# LuMini_8X8.net
KiCad netlist of a schematic drawn in EAGLE
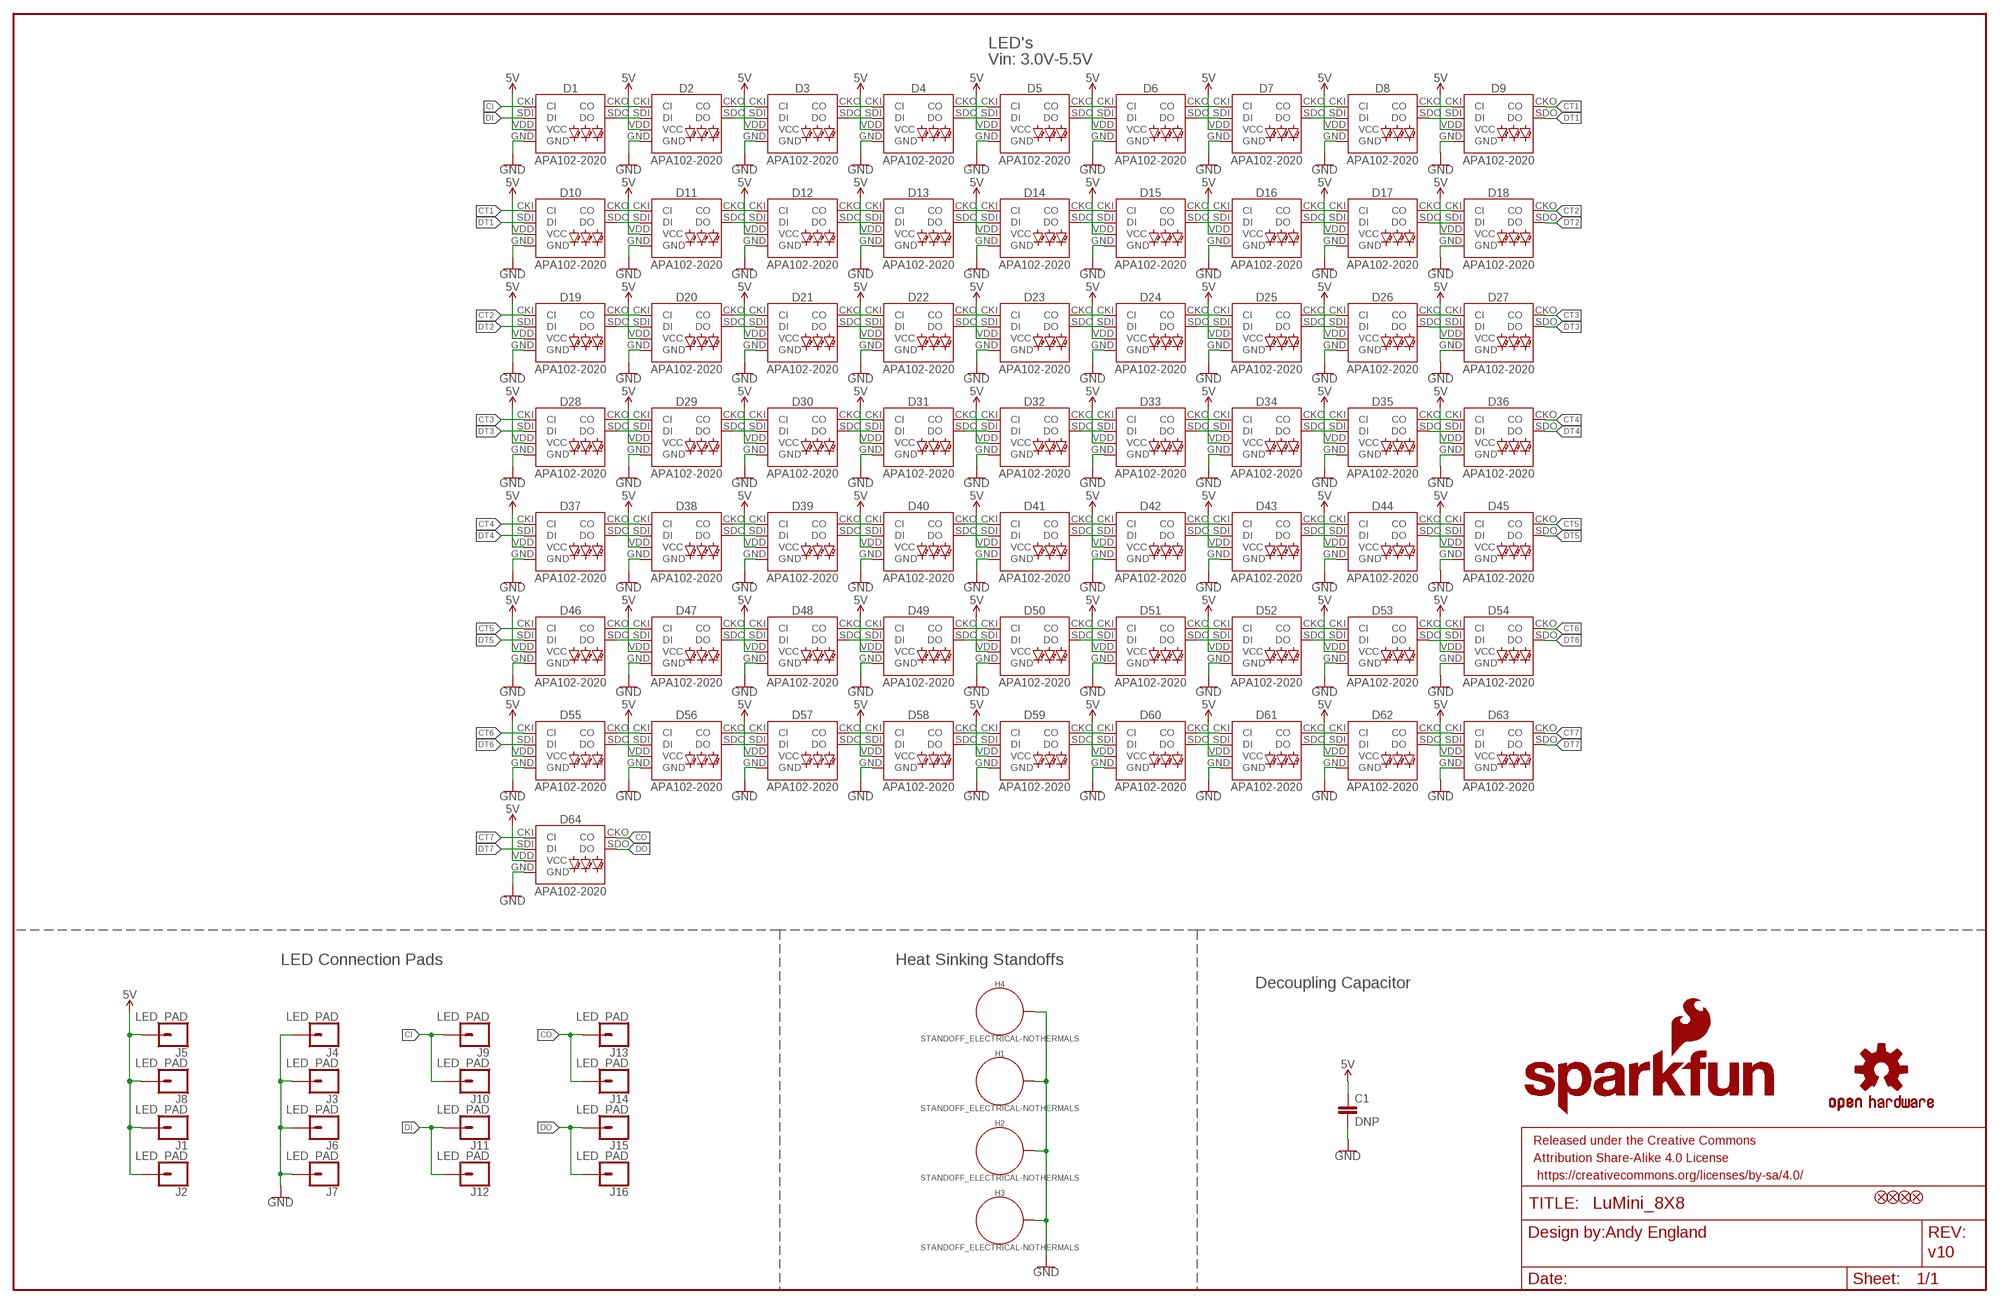
[diagram p0: schematic, sheet 1]

(export (version "E")
  (design (tool "Eeschema 10.0.6"))
  (components
    (comp (ref "C1")
      (value "DNP")
      (footprint "eagle-import:1206")
      (libsource (lib "eagle-import") (part "4.7UF-1206-16V-(+80/-20%)"))
    )
    (comp (ref "D1")
      (value "APA102-2020")
      (footprint "eagle-import:APA102-2020")
      (libsource (lib "eagle-import") (part "APA102-2020"))
    )
    (comp (ref "D2")
      (value "APA102-2020")
      (footprint "eagle-import:APA102-2020")
      (libsource (lib "eagle-import") (part "APA102-2020"))
    )
    (comp (ref "D3")
      (value "APA102-2020")
      (footprint "eagle-import:APA102-2020")
      (libsource (lib "eagle-import") (part "APA102-2020"))
    )
    (comp (ref "D4")
      (value "APA102-2020")
      (footprint "eagle-import:APA102-2020")
      (libsource (lib "eagle-import") (part "APA102-2020"))
    )
    (comp (ref "D5")
      (value "APA102-2020")
      (footprint "eagle-import:APA102-2020")
      (libsource (lib "eagle-import") (part "APA102-2020"))
    )
    (comp (ref "D6")
      (value "APA102-2020")
      (footprint "eagle-import:APA102-2020")
      (libsource (lib "eagle-import") (part "APA102-2020"))
    )
    (comp (ref "D7")
      (value "APA102-2020")
      (footprint "eagle-import:APA102-2020")
      (libsource (lib "eagle-import") (part "APA102-2020"))
    )
    (comp (ref "D8")
      (value "APA102-2020")
      (footprint "eagle-import:APA102-2020")
      (libsource (lib "eagle-import") (part "APA102-2020"))
    )
    (comp (ref "D9")
      (value "APA102-2020")
      (footprint "eagle-import:APA102-2020")
      (libsource (lib "eagle-import") (part "APA102-2020"))
    )
    (comp (ref "D10")
      (value "APA102-2020")
      (footprint "eagle-import:APA102-2020")
      (libsource (lib "eagle-import") (part "APA102-2020"))
    )
    (comp (ref "D11")
      (value "APA102-2020")
      (footprint "eagle-import:APA102-2020")
      (libsource (lib "eagle-import") (part "APA102-2020"))
    )
    (comp (ref "D12")
      (value "APA102-2020")
      (footprint "eagle-import:APA102-2020")
      (libsource (lib "eagle-import") (part "APA102-2020"))
    )
    (comp (ref "D13")
      (value "APA102-2020")
      (footprint "eagle-import:APA102-2020")
      (libsource (lib "eagle-import") (part "APA102-2020"))
    )
    (comp (ref "D14")
      (value "APA102-2020")
      (footprint "eagle-import:APA102-2020")
      (libsource (lib "eagle-import") (part "APA102-2020"))
    )
    (comp (ref "D15")
      (value "APA102-2020")
      (footprint "eagle-import:APA102-2020")
      (libsource (lib "eagle-import") (part "APA102-2020"))
    )
    (comp (ref "D16")
      (value "APA102-2020")
      (footprint "eagle-import:APA102-2020")
      (libsource (lib "eagle-import") (part "APA102-2020"))
    )
    (comp (ref "D17")
      (value "APA102-2020")
      (footprint "eagle-import:APA102-2020")
      (libsource (lib "eagle-import") (part "APA102-2020"))
    )
    (comp (ref "D18")
      (value "APA102-2020")
      (footprint "eagle-import:APA102-2020")
      (libsource (lib "eagle-import") (part "APA102-2020"))
    )
    (comp (ref "D19")
      (value "APA102-2020")
      (footprint "eagle-import:APA102-2020")
      (libsource (lib "eagle-import") (part "APA102-2020"))
    )
    (comp (ref "D20")
      (value "APA102-2020")
      (footprint "eagle-import:APA102-2020")
      (libsource (lib "eagle-import") (part "APA102-2020"))
    )
    (comp (ref "D21")
      (value "APA102-2020")
      (footprint "eagle-import:APA102-2020")
      (libsource (lib "eagle-import") (part "APA102-2020"))
    )
    (comp (ref "D22")
      (value "APA102-2020")
      (footprint "eagle-import:APA102-2020")
      (libsource (lib "eagle-import") (part "APA102-2020"))
    )
    (comp (ref "D23")
      (value "APA102-2020")
      (footprint "eagle-import:APA102-2020")
      (libsource (lib "eagle-import") (part "APA102-2020"))
    )
    (comp (ref "D24")
      (value "APA102-2020")
      (footprint "eagle-import:APA102-2020")
      (libsource (lib "eagle-import") (part "APA102-2020"))
    )
    (comp (ref "D25")
      (value "APA102-2020")
      (footprint "eagle-import:APA102-2020")
      (libsource (lib "eagle-import") (part "APA102-2020"))
    )
    (comp (ref "D26")
      (value "APA102-2020")
      (footprint "eagle-import:APA102-2020")
      (libsource (lib "eagle-import") (part "APA102-2020"))
    )
    (comp (ref "D27")
      (value "APA102-2020")
      (footprint "eagle-import:APA102-2020")
      (libsource (lib "eagle-import") (part "APA102-2020"))
    )
    (comp (ref "D28")
      (value "APA102-2020")
      (footprint "eagle-import:APA102-2020")
      (libsource (lib "eagle-import") (part "APA102-2020"))
    )
    (comp (ref "D29")
      (value "APA102-2020")
      (footprint "eagle-import:APA102-2020")
      (libsource (lib "eagle-import") (part "APA102-2020"))
    )
    (comp (ref "D30")
      (value "APA102-2020")
      (footprint "eagle-import:APA102-2020")
      (libsource (lib "eagle-import") (part "APA102-2020"))
    )
    (comp (ref "D31")
      (value "APA102-2020")
      (footprint "eagle-import:APA102-2020")
      (libsource (lib "eagle-import") (part "APA102-2020"))
    )
    (comp (ref "D32")
      (value "APA102-2020")
      (footprint "eagle-import:APA102-2020")
      (libsource (lib "eagle-import") (part "APA102-2020"))
    )
    (comp (ref "D33")
      (value "APA102-2020")
      (footprint "eagle-import:APA102-2020")
      (libsource (lib "eagle-import") (part "APA102-2020"))
    )
    (comp (ref "D34")
      (value "APA102-2020")
      (footprint "eagle-import:APA102-2020")
      (libsource (lib "eagle-import") (part "APA102-2020"))
    )
    (comp (ref "D35")
      (value "APA102-2020")
      (footprint "eagle-import:APA102-2020")
      (libsource (lib "eagle-import") (part "APA102-2020"))
    )
    (comp (ref "D36")
      (value "APA102-2020")
      (footprint "eagle-import:APA102-2020")
      (libsource (lib "eagle-import") (part "APA102-2020"))
    )
    (comp (ref "D37")
      (value "APA102-2020")
      (footprint "eagle-import:APA102-2020")
      (libsource (lib "eagle-import") (part "APA102-2020"))
    )
    (comp (ref "D38")
      (value "APA102-2020")
      (footprint "eagle-import:APA102-2020")
      (libsource (lib "eagle-import") (part "APA102-2020"))
    )
    (comp (ref "D39")
      (value "APA102-2020")
      (footprint "eagle-import:APA102-2020")
      (libsource (lib "eagle-import") (part "APA102-2020"))
    )
    (comp (ref "D40")
      (value "APA102-2020")
      (footprint "eagle-import:APA102-2020")
      (libsource (lib "eagle-import") (part "APA102-2020"))
    )
    (comp (ref "D41")
      (value "APA102-2020")
      (footprint "eagle-import:APA102-2020")
      (libsource (lib "eagle-import") (part "APA102-2020"))
    )
    (comp (ref "D42")
      (value "APA102-2020")
      (footprint "eagle-import:APA102-2020")
      (libsource (lib "eagle-import") (part "APA102-2020"))
    )
    (comp (ref "D43")
      (value "APA102-2020")
      (footprint "eagle-import:APA102-2020")
      (libsource (lib "eagle-import") (part "APA102-2020"))
    )
    (comp (ref "D44")
      (value "APA102-2020")
      (footprint "eagle-import:APA102-2020")
      (libsource (lib "eagle-import") (part "APA102-2020"))
    )
    (comp (ref "D45")
      (value "APA102-2020")
      (footprint "eagle-import:APA102-2020")
      (libsource (lib "eagle-import") (part "APA102-2020"))
    )
    (comp (ref "D46")
      (value "APA102-2020")
      (footprint "eagle-import:APA102-2020")
      (libsource (lib "eagle-import") (part "APA102-2020"))
    )
    (comp (ref "D47")
      (value "APA102-2020")
      (footprint "eagle-import:APA102-2020")
      (libsource (lib "eagle-import") (part "APA102-2020"))
    )
    (comp (ref "D48")
      (value "APA102-2020")
      (footprint "eagle-import:APA102-2020")
      (libsource (lib "eagle-import") (part "APA102-2020"))
    )
    (comp (ref "D49")
      (value "APA102-2020")
      (footprint "eagle-import:APA102-2020")
      (libsource (lib "eagle-import") (part "APA102-2020"))
    )
    (comp (ref "D50")
      (value "APA102-2020")
      (footprint "eagle-import:APA102-2020")
      (libsource (lib "eagle-import") (part "APA102-2020"))
    )
    (comp (ref "D51")
      (value "APA102-2020")
      (footprint "eagle-import:APA102-2020")
      (libsource (lib "eagle-import") (part "APA102-2020"))
    )
    (comp (ref "D52")
      (value "APA102-2020")
      (footprint "eagle-import:APA102-2020")
      (libsource (lib "eagle-import") (part "APA102-2020"))
    )
    (comp (ref "D53")
      (value "APA102-2020")
      (footprint "eagle-import:APA102-2020")
      (libsource (lib "eagle-import") (part "APA102-2020"))
    )
    (comp (ref "D54")
      (value "APA102-2020")
      (footprint "eagle-import:APA102-2020")
      (libsource (lib "eagle-import") (part "APA102-2020"))
    )
    (comp (ref "D55")
      (value "APA102-2020")
      (footprint "eagle-import:APA102-2020")
      (libsource (lib "eagle-import") (part "APA102-2020"))
    )
    (comp (ref "D56")
      (value "APA102-2020")
      (footprint "eagle-import:APA102-2020")
      (libsource (lib "eagle-import") (part "APA102-2020"))
    )
    (comp (ref "D57")
      (value "APA102-2020")
      (footprint "eagle-import:APA102-2020")
      (libsource (lib "eagle-import") (part "APA102-2020"))
    )
    (comp (ref "D58")
      (value "APA102-2020")
      (footprint "eagle-import:APA102-2020")
      (libsource (lib "eagle-import") (part "APA102-2020"))
    )
    (comp (ref "D59")
      (value "APA102-2020")
      (footprint "eagle-import:APA102-2020")
      (libsource (lib "eagle-import") (part "APA102-2020"))
    )
    (comp (ref "D60")
      (value "APA102-2020")
      (footprint "eagle-import:APA102-2020")
      (libsource (lib "eagle-import") (part "APA102-2020"))
    )
    (comp (ref "D61")
      (value "APA102-2020")
      (footprint "eagle-import:APA102-2020")
      (libsource (lib "eagle-import") (part "APA102-2020"))
    )
    (comp (ref "D62")
      (value "APA102-2020")
      (footprint "eagle-import:APA102-2020")
      (libsource (lib "eagle-import") (part "APA102-2020"))
    )
    (comp (ref "D63")
      (value "APA102-2020")
      (footprint "eagle-import:APA102-2020")
      (libsource (lib "eagle-import") (part "APA102-2020"))
    )
    (comp (ref "D64")
      (value "APA102-2020")
      (footprint "eagle-import:APA102-2020")
      (libsource (lib "eagle-import") (part "APA102-2020"))
    )
    (comp (ref "FD1")
      (value "FIDUCIALUFIDUCIAL")
      (footprint "eagle-import:FIDUCIAL-MICRO")
      (libsource (lib "eagle-import") (part "FIDUCIALUFIDUCIAL"))
    )
    (comp (ref "FD2")
      (value "FIDUCIALUFIDUCIAL")
      (footprint "eagle-import:FIDUCIAL-MICRO")
      (libsource (lib "eagle-import") (part "FIDUCIALUFIDUCIAL"))
    )
    (comp (ref "FD3")
      (value "FIDUCIALUFIDUCIAL")
      (footprint "eagle-import:FIDUCIAL-MICRO")
      (libsource (lib "eagle-import") (part "FIDUCIALUFIDUCIAL"))
    )
    (comp (ref "FD4")
      (value "FIDUCIALUFIDUCIAL")
      (footprint "eagle-import:FIDUCIAL-MICRO")
      (libsource (lib "eagle-import") (part "FIDUCIALUFIDUCIAL"))
    )
    (comp (ref "FRAME1")
      (value "FRAME-LEDGER")
      (footprint "eagle-import:CREATIVE_COMMONS")
      (libsource (lib "eagle-import") (part "FRAME-LEDGER"))
    )
    (comp (ref "H1")
      (value "STANDOFF_ELECTRICAL-NOTHERMALS")
      (footprint "eagle-import:STANDOFF-ELECTRICAL-NOTHERMALS")
      (libsource (lib "eagle-import") (part "STANDOFF_ELECTRICAL-NOTHERMALS"))
    )
    (comp (ref "H2")
      (value "STANDOFF_ELECTRICAL-NOTHERMALS")
      (footprint "eagle-import:STANDOFF-ELECTRICAL-NOTHERMALS")
      (libsource (lib "eagle-import") (part "STANDOFF_ELECTRICAL-NOTHERMALS"))
    )
    (comp (ref "H3")
      (value "STANDOFF_ELECTRICAL-NOTHERMALS")
      (footprint "eagle-import:STANDOFF-ELECTRICAL-NOTHERMALS")
      (libsource (lib "eagle-import") (part "STANDOFF_ELECTRICAL-NOTHERMALS"))
    )
    (comp (ref "H4")
      (value "STANDOFF_ELECTRICAL-NOTHERMALS")
      (footprint "eagle-import:STANDOFF-ELECTRICAL-NOTHERMALS")
      (libsource (lib "eagle-import") (part "STANDOFF_ELECTRICAL-NOTHERMALS"))
    )
    (comp (ref "J1")
      (value "LED_PAD")
      (footprint "eagle-import:CIRCULARPAD")
      (libsource (lib "eagle-import") (part "LED_PAD"))
    )
    (comp (ref "J2")
      (value "LED_PAD")
      (footprint "eagle-import:CIRCULARPAD")
      (libsource (lib "eagle-import") (part "LED_PAD"))
    )
    (comp (ref "J3")
      (value "LED_PAD")
      (footprint "eagle-import:CIRCULARPAD")
      (libsource (lib "eagle-import") (part "LED_PAD"))
    )
    (comp (ref "J4")
      (value "LED_PAD")
      (footprint "eagle-import:CIRCULARPAD")
      (libsource (lib "eagle-import") (part "LED_PAD"))
    )
    (comp (ref "J5")
      (value "LED_PAD")
      (footprint "eagle-import:CIRCULARPAD")
      (libsource (lib "eagle-import") (part "LED_PAD"))
    )
    (comp (ref "J6")
      (value "LED_PAD")
      (footprint "eagle-import:CIRCULARPAD")
      (libsource (lib "eagle-import") (part "LED_PAD"))
    )
    (comp (ref "J7")
      (value "LED_PAD")
      (footprint "eagle-import:CIRCULARPAD")
      (libsource (lib "eagle-import") (part "LED_PAD"))
    )
    (comp (ref "J8")
      (value "LED_PAD")
      (footprint "eagle-import:CIRCULARPAD")
      (libsource (lib "eagle-import") (part "LED_PAD"))
    )
    (comp (ref "J9")
      (value "LED_PAD")
      (footprint "eagle-import:CIRCULARPAD")
      (libsource (lib "eagle-import") (part "LED_PAD"))
    )
    (comp (ref "J10")
      (value "LED_PAD")
      (footprint "eagle-import:CIRCULARPAD")
      (libsource (lib "eagle-import") (part "LED_PAD"))
    )
    (comp (ref "J11")
      (value "LED_PAD")
      (footprint "eagle-import:CIRCULARPAD")
      (libsource (lib "eagle-import") (part "LED_PAD"))
    )
    (comp (ref "J12")
      (value "LED_PAD")
      (footprint "eagle-import:CIRCULARPAD")
      (libsource (lib "eagle-import") (part "LED_PAD"))
    )
    (comp (ref "J13")
      (value "LED_PAD")
      (footprint "eagle-import:CIRCULARPAD")
      (libsource (lib "eagle-import") (part "LED_PAD"))
    )
    (comp (ref "J14")
      (value "LED_PAD")
      (footprint "eagle-import:CIRCULARPAD")
      (libsource (lib "eagle-import") (part "LED_PAD"))
    )
    (comp (ref "J15")
      (value "LED_PAD")
      (footprint "eagle-import:CIRCULARPAD")
      (libsource (lib "eagle-import") (part "LED_PAD"))
    )
    (comp (ref "J16")
      (value "LED_PAD")
      (footprint "eagle-import:CIRCULARPAD")
      (libsource (lib "eagle-import") (part "LED_PAD"))
    )
    (comp (ref "LOGO1")
      (value "SFE_LOGO_NAME_FLAME.1_INCH")
      (footprint "eagle-import:SFE_LOGO_NAME_FLAME_.1")
      (libsource (lib "eagle-import") (part "SFE_LOGO_NAME_FLAME.1_INCH"))
    )
    (comp (ref "LOGO2")
      (value "OSHW-LOGOS")
      (footprint "eagle-import:OSHW-LOGO-S")
      (libsource (lib "eagle-import") (part "OSHW-LOGOS"))
    )
  )
  (nets
    (net (code "1") (name "5V") (class "Default")
      (node (ref "C1") (pin "1") (pinfunction "1_1") (pintype "passive"))
      (node (ref "D1") (pin "VDD") (pinfunction "VCC_VDD") (pintype "bidirectional"))
      (node (ref "D10") (pin "VDD") (pinfunction "VCC_VDD") (pintype "bidirectional"))
      (node (ref "D11") (pin "VDD") (pinfunction "VCC_VDD") (pintype "bidirectional"))
      (node (ref "D12") (pin "VDD") (pinfunction "VCC_VDD") (pintype "bidirectional"))
      (node (ref "D13") (pin "VDD") (pinfunction "VCC_VDD") (pintype "bidirectional"))
      (node (ref "D14") (pin "VDD") (pinfunction "VCC_VDD") (pintype "bidirectional"))
      (node (ref "D15") (pin "VDD") (pinfunction "VCC_VDD") (pintype "bidirectional"))
      (node (ref "D16") (pin "VDD") (pinfunction "VCC_VDD") (pintype "bidirectional"))
      (node (ref "D17") (pin "VDD") (pinfunction "VCC_VDD") (pintype "bidirectional"))
      (node (ref "D18") (pin "VDD") (pinfunction "VCC_VDD") (pintype "bidirectional"))
      (node (ref "D19") (pin "VDD") (pinfunction "VCC_VDD") (pintype "bidirectional"))
      (node (ref "D2") (pin "VDD") (pinfunction "VCC_VDD") (pintype "bidirectional"))
      (node (ref "D20") (pin "VDD") (pinfunction "VCC_VDD") (pintype "bidirectional"))
      (node (ref "D21") (pin "VDD") (pinfunction "VCC_VDD") (pintype "bidirectional"))
      (node (ref "D22") (pin "VDD") (pinfunction "VCC_VDD") (pintype "bidirectional"))
      (node (ref "D23") (pin "VDD") (pinfunction "VCC_VDD") (pintype "bidirectional"))
      (node (ref "D24") (pin "VDD") (pinfunction "VCC_VDD") (pintype "bidirectional"))
      (node (ref "D25") (pin "VDD") (pinfunction "VCC_VDD") (pintype "bidirectional"))
      (node (ref "D26") (pin "VDD") (pinfunction "VCC_VDD") (pintype "bidirectional"))
      (node (ref "D27") (pin "VDD") (pinfunction "VCC_VDD") (pintype "bidirectional"))
      (node (ref "D28") (pin "VDD") (pinfunction "VCC_VDD") (pintype "bidirectional"))
      (node (ref "D29") (pin "VDD") (pinfunction "VCC_VDD") (pintype "bidirectional"))
      (node (ref "D3") (pin "VDD") (pinfunction "VCC_VDD") (pintype "bidirectional"))
      (node (ref "D30") (pin "VDD") (pinfunction "VCC_VDD") (pintype "bidirectional"))
      (node (ref "D31") (pin "VDD") (pinfunction "VCC_VDD") (pintype "bidirectional"))
      (node (ref "D32") (pin "VDD") (pinfunction "VCC_VDD") (pintype "bidirectional"))
      (node (ref "D33") (pin "VDD") (pinfunction "VCC_VDD") (pintype "bidirectional"))
      (node (ref "D34") (pin "VDD") (pinfunction "VCC_VDD") (pintype "bidirectional"))
      (node (ref "D35") (pin "VDD") (pinfunction "VCC_VDD") (pintype "bidirectional"))
      (node (ref "D36") (pin "VDD") (pinfunction "VCC_VDD") (pintype "bidirectional"))
      (node (ref "D37") (pin "VDD") (pinfunction "VCC_VDD") (pintype "bidirectional"))
      (node (ref "D38") (pin "VDD") (pinfunction "VCC_VDD") (pintype "bidirectional"))
      (node (ref "D39") (pin "VDD") (pinfunction "VCC_VDD") (pintype "bidirectional"))
      (node (ref "D4") (pin "VDD") (pinfunction "VCC_VDD") (pintype "bidirectional"))
      (node (ref "D40") (pin "VDD") (pinfunction "VCC_VDD") (pintype "bidirectional"))
      (node (ref "D41") (pin "VDD") (pinfunction "VCC_VDD") (pintype "bidirectional"))
      (node (ref "D42") (pin "VDD") (pinfunction "VCC_VDD") (pintype "bidirectional"))
      (node (ref "D43") (pin "VDD") (pinfunction "VCC_VDD") (pintype "bidirectional"))
      (node (ref "D44") (pin "VDD") (pinfunction "VCC_VDD") (pintype "bidirectional"))
      (node (ref "D45") (pin "VDD") (pinfunction "VCC_VDD") (pintype "bidirectional"))
      (node (ref "D46") (pin "VDD") (pinfunction "VCC_VDD") (pintype "bidirectional"))
      (node (ref "D47") (pin "VDD") (pinfunction "VCC_VDD") (pintype "bidirectional"))
      (node (ref "D48") (pin "VDD") (pinfunction "VCC_VDD") (pintype "bidirectional"))
      (node (ref "D49") (pin "VDD") (pinfunction "VCC_VDD") (pintype "bidirectional"))
      (node (ref "D5") (pin "VDD") (pinfunction "VCC_VDD") (pintype "bidirectional"))
      (node (ref "D50") (pin "VDD") (pinfunction "VCC_VDD") (pintype "bidirectional"))
      (node (ref "D51") (pin "VDD") (pinfunction "VCC_VDD") (pintype "bidirectional"))
      (node (ref "D52") (pin "VDD") (pinfunction "VCC_VDD") (pintype "bidirectional"))
      (node (ref "D53") (pin "VDD") (pinfunction "VCC_VDD") (pintype "bidirectional"))
      (node (ref "D54") (pin "VDD") (pinfunction "VCC_VDD") (pintype "bidirectional"))
      (node (ref "D55") (pin "VDD") (pinfunction "VCC_VDD") (pintype "bidirectional"))
      (node (ref "D56") (pin "VDD") (pinfunction "VCC_VDD") (pintype "bidirectional"))
      (node (ref "D57") (pin "VDD") (pinfunction "VCC_VDD") (pintype "bidirectional"))
      (node (ref "D58") (pin "VDD") (pinfunction "VCC_VDD") (pintype "bidirectional"))
      (node (ref "D59") (pin "VDD") (pinfunction "VCC_VDD") (pintype "bidirectional"))
      (node (ref "D6") (pin "VDD") (pinfunction "VCC_VDD") (pintype "bidirectional"))
      (node (ref "D60") (pin "VDD") (pinfunction "VCC_VDD") (pintype "bidirectional"))
      (node (ref "D61") (pin "VDD") (pinfunction "VCC_VDD") (pintype "bidirectional"))
      (node (ref "D62") (pin "VDD") (pinfunction "VCC_VDD") (pintype "bidirectional"))
      (node (ref "D63") (pin "VDD") (pinfunction "VCC_VDD") (pintype "bidirectional"))
      (node (ref "D64") (pin "VDD") (pinfunction "VCC_VDD") (pintype "bidirectional"))
      (node (ref "D7") (pin "VDD") (pinfunction "VCC_VDD") (pintype "bidirectional"))
      (node (ref "D8") (pin "VDD") (pinfunction "VCC_VDD") (pintype "bidirectional"))
      (node (ref "D9") (pin "VDD") (pinfunction "VCC_VDD") (pintype "bidirectional"))
      (node (ref "J1") (pin "P$1") (pinfunction "1_P$1") (pintype "passive"))
      (node (ref "J1") (pin "P$2") (pinfunction "1_P$2") (pintype "passive"))
      (node (ref "J2") (pin "P$1") (pinfunction "1_P$1") (pintype "passive"))
      (node (ref "J2") (pin "P$2") (pinfunction "1_P$2") (pintype "passive"))
      (node (ref "J5") (pin "P$1") (pinfunction "1_P$1") (pintype "passive"))
      (node (ref "J5") (pin "P$2") (pinfunction "1_P$2") (pintype "passive"))
      (node (ref "J8") (pin "P$1") (pinfunction "1_P$1") (pintype "passive"))
      (node (ref "J8") (pin "P$2") (pinfunction "1_P$2") (pintype "passive"))
    )
    (net (code "2") (name "CI") (class "Default")
      (node (ref "D1") (pin "CKI") (pinfunction "CI_CKI") (pintype "bidirectional"))
      (node (ref "J10") (pin "P$1") (pinfunction "1_P$1") (pintype "passive"))
      (node (ref "J10") (pin "P$2") (pinfunction "1_P$2") (pintype "passive"))
      (node (ref "J9") (pin "P$1") (pinfunction "1_P$1") (pintype "passive"))
      (node (ref "J9") (pin "P$2") (pinfunction "1_P$2") (pintype "passive"))
    )
    (net (code "3") (name "CO") (class "Default")
      (node (ref "D64") (pin "CKO") (pinfunction "CO_CKO") (pintype "bidirectional"))
      (node (ref "J13") (pin "P$1") (pinfunction "1_P$1") (pintype "passive"))
      (node (ref "J13") (pin "P$2") (pinfunction "1_P$2") (pintype "passive"))
      (node (ref "J14") (pin "P$1") (pinfunction "1_P$1") (pintype "passive"))
      (node (ref "J14") (pin "P$2") (pinfunction "1_P$2") (pintype "passive"))
    )
    (net (code "4") (name "CT1") (class "Default")
      (node (ref "D10") (pin "CKI") (pinfunction "CI_CKI") (pintype "bidirectional"))
      (node (ref "D9") (pin "CKO") (pinfunction "CO_CKO") (pintype "bidirectional"))
    )
    (net (code "5") (name "CT2") (class "Default")
      (node (ref "D18") (pin "CKO") (pinfunction "CO_CKO") (pintype "bidirectional"))
      (node (ref "D19") (pin "CKI") (pinfunction "CI_CKI") (pintype "bidirectional"))
    )
    (net (code "6") (name "CT3") (class "Default")
      (node (ref "D27") (pin "CKO") (pinfunction "CO_CKO") (pintype "bidirectional"))
      (node (ref "D28") (pin "CKI") (pinfunction "CI_CKI") (pintype "bidirectional"))
    )
    (net (code "7") (name "CT4") (class "Default")
      (node (ref "D36") (pin "CKO") (pinfunction "CO_CKO") (pintype "bidirectional"))
      (node (ref "D37") (pin "CKI") (pinfunction "CI_CKI") (pintype "bidirectional"))
    )
    (net (code "8") (name "CT5") (class "Default")
      (node (ref "D45") (pin "CKO") (pinfunction "CO_CKO") (pintype "bidirectional"))
      (node (ref "D46") (pin "CKI") (pinfunction "CI_CKI") (pintype "bidirectional"))
    )
    (net (code "9") (name "CT6") (class "Default")
      (node (ref "D54") (pin "CKO") (pinfunction "CO_CKO") (pintype "bidirectional"))
      (node (ref "D55") (pin "CKI") (pinfunction "CI_CKI") (pintype "bidirectional"))
    )
    (net (code "10") (name "CT7") (class "Default")
      (node (ref "D63") (pin "CKO") (pinfunction "CO_CKO") (pintype "bidirectional"))
      (node (ref "D64") (pin "CKI") (pinfunction "CI_CKI") (pintype "bidirectional"))
    )
    (net (code "11") (name "DI") (class "Default")
      (node (ref "D1") (pin "SDI") (pinfunction "DI_SDI") (pintype "bidirectional"))
      (node (ref "J11") (pin "P$1") (pinfunction "1_P$1") (pintype "passive"))
      (node (ref "J11") (pin "P$2") (pinfunction "1_P$2") (pintype "passive"))
      (node (ref "J12") (pin "P$1") (pinfunction "1_P$1") (pintype "passive"))
      (node (ref "J12") (pin "P$2") (pinfunction "1_P$2") (pintype "passive"))
    )
    (net (code "12") (name "DO") (class "Default")
      (node (ref "D64") (pin "SDO") (pinfunction "DO_SDO") (pintype "bidirectional"))
      (node (ref "J15") (pin "P$1") (pinfunction "1_P$1") (pintype "passive"))
      (node (ref "J15") (pin "P$2") (pinfunction "1_P$2") (pintype "passive"))
      (node (ref "J16") (pin "P$1") (pinfunction "1_P$1") (pintype "passive"))
      (node (ref "J16") (pin "P$2") (pinfunction "1_P$2") (pintype "passive"))
    )
    (net (code "13") (name "DT1") (class "Default")
      (node (ref "D10") (pin "SDI") (pinfunction "DI_SDI") (pintype "bidirectional"))
      (node (ref "D9") (pin "SDO") (pinfunction "DO_SDO") (pintype "bidirectional"))
    )
    (net (code "14") (name "DT2") (class "Default")
      (node (ref "D18") (pin "SDO") (pinfunction "DO_SDO") (pintype "bidirectional"))
      (node (ref "D19") (pin "SDI") (pinfunction "DI_SDI") (pintype "bidirectional"))
    )
    (net (code "15") (name "DT3") (class "Default")
      (node (ref "D27") (pin "SDO") (pinfunction "DO_SDO") (pintype "bidirectional"))
      (node (ref "D28") (pin "SDI") (pinfunction "DI_SDI") (pintype "bidirectional"))
    )
    (net (code "16") (name "DT4") (class "Default")
      (node (ref "D36") (pin "SDO") (pinfunction "DO_SDO") (pintype "bidirectional"))
      (node (ref "D37") (pin "SDI") (pinfunction "DI_SDI") (pintype "bidirectional"))
    )
    (net (code "17") (name "DT5") (class "Default")
      (node (ref "D45") (pin "SDO") (pinfunction "DO_SDO") (pintype "bidirectional"))
      (node (ref "D46") (pin "SDI") (pinfunction "DI_SDI") (pintype "bidirectional"))
    )
    (net (code "18") (name "DT6") (class "Default")
      (node (ref "D54") (pin "SDO") (pinfunction "DO_SDO") (pintype "bidirectional"))
      (node (ref "D55") (pin "SDI") (pinfunction "DI_SDI") (pintype "bidirectional"))
    )
    (net (code "19") (name "DT7") (class "Default")
      (node (ref "D63") (pin "SDO") (pinfunction "DO_SDO") (pintype "bidirectional"))
      (node (ref "D64") (pin "SDI") (pinfunction "DI_SDI") (pintype "bidirectional"))
    )
    (net (code "20") (name "GND") (class "Default")
      (node (ref "C1") (pin "2") (pinfunction "2_2") (pintype "passive"))
      (node (ref "D1") (pin "GND") (pinfunction "GND_GND") (pintype "bidirectional"))
      (node (ref "D10") (pin "GND") (pinfunction "GND_GND") (pintype "bidirectional"))
      (node (ref "D11") (pin "GND") (pinfunction "GND_GND") (pintype "bidirectional"))
      (node (ref "D12") (pin "GND") (pinfunction "GND_GND") (pintype "bidirectional"))
      (node (ref "D13") (pin "GND") (pinfunction "GND_GND") (pintype "bidirectional"))
      (node (ref "D14") (pin "GND") (pinfunction "GND_GND") (pintype "bidirectional"))
      (node (ref "D15") (pin "GND") (pinfunction "GND_GND") (pintype "bidirectional"))
      (node (ref "D16") (pin "GND") (pinfunction "GND_GND") (pintype "bidirectional"))
      (node (ref "D17") (pin "GND") (pinfunction "GND_GND") (pintype "bidirectional"))
      (node (ref "D18") (pin "GND") (pinfunction "GND_GND") (pintype "bidirectional"))
      (node (ref "D19") (pin "GND") (pinfunction "GND_GND") (pintype "bidirectional"))
      (node (ref "D2") (pin "GND") (pinfunction "GND_GND") (pintype "bidirectional"))
      (node (ref "D20") (pin "GND") (pinfunction "GND_GND") (pintype "bidirectional"))
      (node (ref "D21") (pin "GND") (pinfunction "GND_GND") (pintype "bidirectional"))
      (node (ref "D22") (pin "GND") (pinfunction "GND_GND") (pintype "bidirectional"))
      (node (ref "D23") (pin "GND") (pinfunction "GND_GND") (pintype "bidirectional"))
      (node (ref "D24") (pin "GND") (pinfunction "GND_GND") (pintype "bidirectional"))
      (node (ref "D25") (pin "GND") (pinfunction "GND_GND") (pintype "bidirectional"))
      (node (ref "D26") (pin "GND") (pinfunction "GND_GND") (pintype "bidirectional"))
      (node (ref "D27") (pin "GND") (pinfunction "GND_GND") (pintype "bidirectional"))
      (node (ref "D28") (pin "GND") (pinfunction "GND_GND") (pintype "bidirectional"))
      (node (ref "D29") (pin "GND") (pinfunction "GND_GND") (pintype "bidirectional"))
      (node (ref "D3") (pin "GND") (pinfunction "GND_GND") (pintype "bidirectional"))
      (node (ref "D30") (pin "GND") (pinfunction "GND_GND") (pintype "bidirectional"))
      (node (ref "D31") (pin "GND") (pinfunction "GND_GND") (pintype "bidirectional"))
      (node (ref "D32") (pin "GND") (pinfunction "GND_GND") (pintype "bidirectional"))
      (node (ref "D33") (pin "GND") (pinfunction "GND_GND") (pintype "bidirectional"))
      (node (ref "D34") (pin "GND") (pinfunction "GND_GND") (pintype "bidirectional"))
      (node (ref "D35") (pin "GND") (pinfunction "GND_GND") (pintype "bidirectional"))
      (node (ref "D36") (pin "GND") (pinfunction "GND_GND") (pintype "bidirectional"))
      (node (ref "D37") (pin "GND") (pinfunction "GND_GND") (pintype "bidirectional"))
      (node (ref "D38") (pin "GND") (pinfunction "GND_GND") (pintype "bidirectional"))
      (node (ref "D39") (pin "GND") (pinfunction "GND_GND") (pintype "bidirectional"))
      (node (ref "D4") (pin "GND") (pinfunction "GND_GND") (pintype "bidirectional"))
      (node (ref "D40") (pin "GND") (pinfunction "GND_GND") (pintype "bidirectional"))
      (node (ref "D41") (pin "GND") (pinfunction "GND_GND") (pintype "bidirectional"))
      (node (ref "D42") (pin "GND") (pinfunction "GND_GND") (pintype "bidirectional"))
      (node (ref "D43") (pin "GND") (pinfunction "GND_GND") (pintype "bidirectional"))
      (node (ref "D44") (pin "GND") (pinfunction "GND_GND") (pintype "bidirectional"))
      (node (ref "D45") (pin "GND") (pinfunction "GND_GND") (pintype "bidirectional"))
      (node (ref "D46") (pin "GND") (pinfunction "GND_GND") (pintype "bidirectional"))
      (node (ref "D47") (pin "GND") (pinfunction "GND_GND") (pintype "bidirectional"))
      (node (ref "D48") (pin "GND") (pinfunction "GND_GND") (pintype "bidirectional"))
      (node (ref "D49") (pin "GND") (pinfunction "GND_GND") (pintype "bidirectional"))
      (node (ref "D5") (pin "GND") (pinfunction "GND_GND") (pintype "bidirectional"))
      (node (ref "D50") (pin "GND") (pinfunction "GND_GND") (pintype "bidirectional"))
      (node (ref "D51") (pin "GND") (pinfunction "GND_GND") (pintype "bidirectional"))
      (node (ref "D52") (pin "GND") (pinfunction "GND_GND") (pintype "bidirectional"))
      (node (ref "D53") (pin "GND") (pinfunction "GND_GND") (pintype "bidirectional"))
      (node (ref "D54") (pin "GND") (pinfunction "GND_GND") (pintype "bidirectional"))
      (node (ref "D55") (pin "GND") (pinfunction "GND_GND") (pintype "bidirectional"))
      (node (ref "D56") (pin "GND") (pinfunction "GND_GND") (pintype "bidirectional"))
      (node (ref "D57") (pin "GND") (pinfunction "GND_GND") (pintype "bidirectional"))
      (node (ref "D58") (pin "GND") (pinfunction "GND_GND") (pintype "bidirectional"))
      (node (ref "D59") (pin "GND") (pinfunction "GND_GND") (pintype "bidirectional"))
      (node (ref "D6") (pin "GND") (pinfunction "GND_GND") (pintype "bidirectional"))
      (node (ref "D60") (pin "GND") (pinfunction "GND_GND") (pintype "bidirectional"))
      (node (ref "D61") (pin "GND") (pinfunction "GND_GND") (pintype "bidirectional"))
      (node (ref "D62") (pin "GND") (pinfunction "GND_GND") (pintype "bidirectional"))
      (node (ref "D63") (pin "GND") (pinfunction "GND_GND") (pintype "bidirectional"))
      (node (ref "D64") (pin "GND") (pinfunction "GND_GND") (pintype "bidirectional"))
      (node (ref "D7") (pin "GND") (pinfunction "GND_GND") (pintype "bidirectional"))
      (node (ref "D8") (pin "GND") (pinfunction "GND_GND") (pintype "bidirectional"))
      (node (ref "D9") (pin "GND") (pinfunction "GND_GND") (pintype "bidirectional"))
      (node (ref "H1") (pin "P1") (pinfunction "P$1_P1") (pintype "bidirectional"))
      (node (ref "H2") (pin "P1") (pinfunction "P$1_P1") (pintype "bidirectional"))
      (node (ref "H3") (pin "P1") (pinfunction "P$1_P1") (pintype "bidirectional"))
      (node (ref "H4") (pin "P1") (pinfunction "P$1_P1") (pintype "bidirectional"))
      (node (ref "J3") (pin "P$1") (pinfunction "1_P$1") (pintype "passive"))
      (node (ref "J3") (pin "P$2") (pinfunction "1_P$2") (pintype "passive"))
      (node (ref "J4") (pin "P$1") (pinfunction "1_P$1") (pintype "passive"))
      (node (ref "J4") (pin "P$2") (pinfunction "1_P$2") (pintype "passive"))
      (node (ref "J6") (pin "P$1") (pinfunction "1_P$1") (pintype "passive"))
      (node (ref "J6") (pin "P$2") (pinfunction "1_P$2") (pintype "passive"))
      (node (ref "J7") (pin "P$1") (pinfunction "1_P$1") (pintype "passive"))
      (node (ref "J7") (pin "P$2") (pinfunction "1_P$2") (pintype "passive"))
    )
    (net (code "21") (name "Net-(D1-CO)") (class "Default")
      (node (ref "D1") (pin "CKO") (pinfunction "CO_CKO") (pintype "bidirectional"))
      (node (ref "D2") (pin "CKI") (pinfunction "CI_CKI") (pintype "bidirectional"))
    )
    (net (code "22") (name "Net-(D1-DO)") (class "Default")
      (node (ref "D1") (pin "SDO") (pinfunction "DO_SDO") (pintype "bidirectional"))
      (node (ref "D2") (pin "SDI") (pinfunction "DI_SDI") (pintype "bidirectional"))
    )
    (net (code "23") (name "Net-(D2-CO)") (class "Default")
      (node (ref "D2") (pin "CKO") (pinfunction "CO_CKO") (pintype "bidirectional"))
      (node (ref "D3") (pin "CKI") (pinfunction "CI_CKI") (pintype "bidirectional"))
    )
    (net (code "24") (name "Net-(D2-DO)") (class "Default")
      (node (ref "D2") (pin "SDO") (pinfunction "DO_SDO") (pintype "bidirectional"))
      (node (ref "D3") (pin "SDI") (pinfunction "DI_SDI") (pintype "bidirectional"))
    )
    (net (code "25") (name "Net-(D3-CO)") (class "Default")
      (node (ref "D3") (pin "CKO") (pinfunction "CO_CKO") (pintype "bidirectional"))
      (node (ref "D4") (pin "CKI") (pinfunction "CI_CKI") (pintype "bidirectional"))
    )
    (net (code "26") (name "Net-(D3-DO)") (class "Default")
      (node (ref "D3") (pin "SDO") (pinfunction "DO_SDO") (pintype "bidirectional"))
      (node (ref "D4") (pin "SDI") (pinfunction "DI_SDI") (pintype "bidirectional"))
    )
    (net (code "27") (name "Net-(D4-CO)") (class "Default")
      (node (ref "D4") (pin "CKO") (pinfunction "CO_CKO") (pintype "bidirectional"))
      (node (ref "D5") (pin "CKI") (pinfunction "CI_CKI") (pintype "bidirectional"))
    )
    (net (code "28") (name "Net-(D4-DO)") (class "Default")
      (node (ref "D4") (pin "SDO") (pinfunction "DO_SDO") (pintype "bidirectional"))
      (node (ref "D5") (pin "SDI") (pinfunction "DI_SDI") (pintype "bidirectional"))
    )
    (net (code "29") (name "Net-(D5-CO)") (class "Default")
      (node (ref "D5") (pin "CKO") (pinfunction "CO_CKO") (pintype "bidirectional"))
      (node (ref "D6") (pin "CKI") (pinfunction "CI_CKI") (pintype "bidirectional"))
    )
    (net (code "30") (name "Net-(D5-DO)") (class "Default")
      (node (ref "D5") (pin "SDO") (pinfunction "DO_SDO") (pintype "bidirectional"))
      (node (ref "D6") (pin "SDI") (pinfunction "DI_SDI") (pintype "bidirectional"))
    )
    (net (code "31") (name "Net-(D6-CO)") (class "Default")
      (node (ref "D6") (pin "CKO") (pinfunction "CO_CKO") (pintype "bidirectional"))
      (node (ref "D7") (pin "CKI") (pinfunction "CI_CKI") (pintype "bidirectional"))
    )
    (net (code "32") (name "Net-(D6-DO)") (class "Default")
      (node (ref "D6") (pin "SDO") (pinfunction "DO_SDO") (pintype "bidirectional"))
      (node (ref "D7") (pin "SDI") (pinfunction "DI_SDI") (pintype "bidirectional"))
    )
    (net (code "33") (name "Net-(D7-CO)") (class "Default")
      (node (ref "D7") (pin "CKO") (pinfunction "CO_CKO") (pintype "bidirectional"))
      (node (ref "D8") (pin "CKI") (pinfunction "CI_CKI") (pintype "bidirectional"))
    )
    (net (code "34") (name "Net-(D7-DO)") (class "Default")
      (node (ref "D7") (pin "SDO") (pinfunction "DO_SDO") (pintype "bidirectional"))
      (node (ref "D8") (pin "SDI") (pinfunction "DI_SDI") (pintype "bidirectional"))
    )
    (net (code "35") (name "Net-(D8-CO)") (class "Default")
      (node (ref "D8") (pin "CKO") (pinfunction "CO_CKO") (pintype "bidirectional"))
      (node (ref "D9") (pin "CKI") (pinfunction "CI_CKI") (pintype "bidirectional"))
    )
    (net (code "36") (name "Net-(D8-DO)") (class "Default")
      (node (ref "D8") (pin "SDO") (pinfunction "DO_SDO") (pintype "bidirectional"))
      (node (ref "D9") (pin "SDI") (pinfunction "DI_SDI") (pintype "bidirectional"))
    )
    (net (code "37") (name "Net-(D10-CO)") (class "Default")
      (node (ref "D10") (pin "CKO") (pinfunction "CO_CKO") (pintype "bidirectional"))
      (node (ref "D11") (pin "CKI") (pinfunction "CI_CKI") (pintype "bidirectional"))
    )
    (net (code "38") (name "Net-(D10-DO)") (class "Default")
      (node (ref "D10") (pin "SDO") (pinfunction "DO_SDO") (pintype "bidirectional"))
      (node (ref "D11") (pin "SDI") (pinfunction "DI_SDI") (pintype "bidirectional"))
    )
    (net (code "39") (name "Net-(D11-CO)") (class "Default")
      (node (ref "D11") (pin "CKO") (pinfunction "CO_CKO") (pintype "bidirectional"))
      (node (ref "D12") (pin "CKI") (pinfunction "CI_CKI") (pintype "bidirectional"))
    )
    (net (code "40") (name "Net-(D11-DO)") (class "Default")
      (node (ref "D11") (pin "SDO") (pinfunction "DO_SDO") (pintype "bidirectional"))
      (node (ref "D12") (pin "SDI") (pinfunction "DI_SDI") (pintype "bidirectional"))
    )
    (net (code "41") (name "Net-(D12-CO)") (class "Default")
      (node (ref "D12") (pin "CKO") (pinfunction "CO_CKO") (pintype "bidirectional"))
      (node (ref "D13") (pin "CKI") (pinfunction "CI_CKI") (pintype "bidirectional"))
    )
    (net (code "42") (name "Net-(D12-DO)") (class "Default")
      (node (ref "D12") (pin "SDO") (pinfunction "DO_SDO") (pintype "bidirectional"))
      (node (ref "D13") (pin "SDI") (pinfunction "DI_SDI") (pintype "bidirectional"))
    )
    (net (code "43") (name "Net-(D13-CO)") (class "Default")
      (node (ref "D13") (pin "CKO") (pinfunction "CO_CKO") (pintype "bidirectional"))
      (node (ref "D14") (pin "CKI") (pinfunction "CI_CKI") (pintype "bidirectional"))
    )
    (net (code "44") (name "Net-(D13-DO)") (class "Default")
      (node (ref "D13") (pin "SDO") (pinfunction "DO_SDO") (pintype "bidirectional"))
      (node (ref "D14") (pin "SDI") (pinfunction "DI_SDI") (pintype "bidirectional"))
    )
    (net (code "45") (name "Net-(D14-CO)") (class "Default")
      (node (ref "D14") (pin "CKO") (pinfunction "CO_CKO") (pintype "bidirectional"))
      (node (ref "D15") (pin "CKI") (pinfunction "CI_CKI") (pintype "bidirectional"))
    )
    (net (code "46") (name "Net-(D14-DO)") (class "Default")
      (node (ref "D14") (pin "SDO") (pinfunction "DO_SDO") (pintype "bidirectional"))
      (node (ref "D15") (pin "SDI") (pinfunction "DI_SDI") (pintype "bidirectional"))
    )
    (net (code "47") (name "Net-(D15-CO)") (class "Default")
      (node (ref "D15") (pin "CKO") (pinfunction "CO_CKO") (pintype "bidirectional"))
      (node (ref "D16") (pin "CKI") (pinfunction "CI_CKI") (pintype "bidirectional"))
    )
    (net (code "48") (name "Net-(D15-DO)") (class "Default")
      (node (ref "D15") (pin "SDO") (pinfunction "DO_SDO") (pintype "bidirectional"))
      (node (ref "D16") (pin "SDI") (pinfunction "DI_SDI") (pintype "bidirectional"))
    )
    (net (code "49") (name "Net-(D16-CO)") (class "Default")
      (node (ref "D16") (pin "CKO") (pinfunction "CO_CKO") (pintype "bidirectional"))
      (node (ref "D17") (pin "CKI") (pinfunction "CI_CKI") (pintype "bidirectional"))
    )
    (net (code "50") (name "Net-(D16-DO)") (class "Default")
      (node (ref "D16") (pin "SDO") (pinfunction "DO_SDO") (pintype "bidirectional"))
      (node (ref "D17") (pin "SDI") (pinfunction "DI_SDI") (pintype "bidirectional"))
    )
    (net (code "51") (name "Net-(D17-CO)") (class "Default")
      (node (ref "D17") (pin "CKO") (pinfunction "CO_CKO") (pintype "bidirectional"))
      (node (ref "D18") (pin "CKI") (pinfunction "CI_CKI") (pintype "bidirectional"))
    )
    (net (code "52") (name "Net-(D17-DO)") (class "Default")
      (node (ref "D17") (pin "SDO") (pinfunction "DO_SDO") (pintype "bidirectional"))
      (node (ref "D18") (pin "SDI") (pinfunction "DI_SDI") (pintype "bidirectional"))
    )
    (net (code "53") (name "Net-(D19-CO)") (class "Default")
      (node (ref "D19") (pin "CKO") (pinfunction "CO_CKO") (pintype "bidirectional"))
      (node (ref "D20") (pin "CKI") (pinfunction "CI_CKI") (pintype "bidirectional"))
    )
    (net (code "54") (name "Net-(D19-DO)") (class "Default")
      (node (ref "D19") (pin "SDO") (pinfunction "DO_SDO") (pintype "bidirectional"))
      (node (ref "D20") (pin "SDI") (pinfunction "DI_SDI") (pintype "bidirectional"))
    )
    (net (code "55") (name "Net-(D20-CO)") (class "Default")
      (node (ref "D20") (pin "CKO") (pinfunction "CO_CKO") (pintype "bidirectional"))
      (node (ref "D21") (pin "CKI") (pinfunction "CI_CKI") (pintype "bidirectional"))
    )
    (net (code "56") (name "Net-(D20-DO)") (class "Default")
      (node (ref "D20") (pin "SDO") (pinfunction "DO_SDO") (pintype "bidirectional"))
      (node (ref "D21") (pin "SDI") (pinfunction "DI_SDI") (pintype "bidirectional"))
    )
    (net (code "57") (name "Net-(D21-CO)") (class "Default")
      (node (ref "D21") (pin "CKO") (pinfunction "CO_CKO") (pintype "bidirectional"))
      (node (ref "D22") (pin "CKI") (pinfunction "CI_CKI") (pintype "bidirectional"))
    )
    (net (code "58") (name "Net-(D21-DO)") (class "Default")
      (node (ref "D21") (pin "SDO") (pinfunction "DO_SDO") (pintype "bidirectional"))
      (node (ref "D22") (pin "SDI") (pinfunction "DI_SDI") (pintype "bidirectional"))
    )
    (net (code "59") (name "Net-(D22-CO)") (class "Default")
      (node (ref "D22") (pin "CKO") (pinfunction "CO_CKO") (pintype "bidirectional"))
      (node (ref "D23") (pin "CKI") (pinfunction "CI_CKI") (pintype "bidirectional"))
    )
    (net (code "60") (name "Net-(D22-DO)") (class "Default")
      (node (ref "D22") (pin "SDO") (pinfunction "DO_SDO") (pintype "bidirectional"))
      (node (ref "D23") (pin "SDI") (pinfunction "DI_SDI") (pintype "bidirectional"))
    )
    (net (code "61") (name "Net-(D23-CO)") (class "Default")
      (node (ref "D23") (pin "CKO") (pinfunction "CO_CKO") (pintype "bidirectional"))
      (node (ref "D24") (pin "CKI") (pinfunction "CI_CKI") (pintype "bidirectional"))
    )
    (net (code "62") (name "Net-(D23-DO)") (class "Default")
      (node (ref "D23") (pin "SDO") (pinfunction "DO_SDO") (pintype "bidirectional"))
      (node (ref "D24") (pin "SDI") (pinfunction "DI_SDI") (pintype "bidirectional"))
    )
    (net (code "63") (name "Net-(D24-CO)") (class "Default")
      (node (ref "D24") (pin "CKO") (pinfunction "CO_CKO") (pintype "bidirectional"))
      (node (ref "D25") (pin "CKI") (pinfunction "CI_CKI") (pintype "bidirectional"))
    )
    (net (code "64") (name "Net-(D24-DO)") (class "Default")
      (node (ref "D24") (pin "SDO") (pinfunction "DO_SDO") (pintype "bidirectional"))
      (node (ref "D25") (pin "SDI") (pinfunction "DI_SDI") (pintype "bidirectional"))
    )
    (net (code "65") (name "Net-(D25-CO)") (class "Default")
      (node (ref "D25") (pin "CKO") (pinfunction "CO_CKO") (pintype "bidirectional"))
      (node (ref "D26") (pin "CKI") (pinfunction "CI_CKI") (pintype "bidirectional"))
    )
    (net (code "66") (name "Net-(D25-DO)") (class "Default")
      (node (ref "D25") (pin "SDO") (pinfunction "DO_SDO") (pintype "bidirectional"))
      (node (ref "D26") (pin "SDI") (pinfunction "DI_SDI") (pintype "bidirectional"))
    )
    (net (code "67") (name "Net-(D26-CO)") (class "Default")
      (node (ref "D26") (pin "CKO") (pinfunction "CO_CKO") (pintype "bidirectional"))
      (node (ref "D27") (pin "CKI") (pinfunction "CI_CKI") (pintype "bidirectional"))
    )
    (net (code "68") (name "Net-(D26-DO)") (class "Default")
      (node (ref "D26") (pin "SDO") (pinfunction "DO_SDO") (pintype "bidirectional"))
      (node (ref "D27") (pin "SDI") (pinfunction "DI_SDI") (pintype "bidirectional"))
    )
    (net (code "69") (name "Net-(D28-CO)") (class "Default")
      (node (ref "D28") (pin "CKO") (pinfunction "CO_CKO") (pintype "bidirectional"))
      (node (ref "D29") (pin "CKI") (pinfunction "CI_CKI") (pintype "bidirectional"))
    )
    (net (code "70") (name "Net-(D28-DO)") (class "Default")
      (node (ref "D28") (pin "SDO") (pinfunction "DO_SDO") (pintype "bidirectional"))
      (node (ref "D29") (pin "SDI") (pinfunction "DI_SDI") (pintype "bidirectional"))
    )
    (net (code "71") (name "Net-(D29-CO)") (class "Default")
      (node (ref "D29") (pin "CKO") (pinfunction "CO_CKO") (pintype "bidirectional"))
      (node (ref "D30") (pin "CKI") (pinfunction "CI_CKI") (pintype "bidirectional"))
    )
    (net (code "72") (name "Net-(D29-DO)") (class "Default")
      (node (ref "D29") (pin "SDO") (pinfunction "DO_SDO") (pintype "bidirectional"))
      (node (ref "D30") (pin "SDI") (pinfunction "DI_SDI") (pintype "bidirectional"))
    )
    (net (code "73") (name "Net-(D30-CO)") (class "Default")
      (node (ref "D30") (pin "CKO") (pinfunction "CO_CKO") (pintype "bidirectional"))
      (node (ref "D31") (pin "CKI") (pinfunction "CI_CKI") (pintype "bidirectional"))
    )
    (net (code "74") (name "Net-(D30-DO)") (class "Default")
      (node (ref "D30") (pin "SDO") (pinfunction "DO_SDO") (pintype "bidirectional"))
      (node (ref "D31") (pin "SDI") (pinfunction "DI_SDI") (pintype "bidirectional"))
    )
    (net (code "75") (name "Net-(D31-CO)") (class "Default")
      (node (ref "D31") (pin "CKO") (pinfunction "CO_CKO") (pintype "bidirectional"))
      (node (ref "D32") (pin "CKI") (pinfunction "CI_CKI") (pintype "bidirectional"))
    )
    (net (code "76") (name "Net-(D31-DO)") (class "Default")
      (node (ref "D31") (pin "SDO") (pinfunction "DO_SDO") (pintype "bidirectional"))
      (node (ref "D32") (pin "SDI") (pinfunction "DI_SDI") (pintype "bidirectional"))
    )
    (net (code "77") (name "Net-(D32-CO)") (class "Default")
      (node (ref "D32") (pin "CKO") (pinfunction "CO_CKO") (pintype "bidirectional"))
      (node (ref "D33") (pin "CKI") (pinfunction "CI_CKI") (pintype "bidirectional"))
    )
    (net (code "78") (name "Net-(D32-DO)") (class "Default")
      (node (ref "D32") (pin "SDO") (pinfunction "DO_SDO") (pintype "bidirectional"))
      (node (ref "D33") (pin "SDI") (pinfunction "DI_SDI") (pintype "bidirectional"))
    )
    (net (code "79") (name "Net-(D33-CO)") (class "Default")
      (node (ref "D33") (pin "CKO") (pinfunction "CO_CKO") (pintype "bidirectional"))
      (node (ref "D34") (pin "CKI") (pinfunction "CI_CKI") (pintype "bidirectional"))
    )
    (net (code "80") (name "Net-(D33-DO)") (class "Default")
      (node (ref "D33") (pin "SDO") (pinfunction "DO_SDO") (pintype "bidirectional"))
      (node (ref "D34") (pin "SDI") (pinfunction "DI_SDI") (pintype "bidirectional"))
    )
    (net (code "81") (name "Net-(D34-CO)") (class "Default")
      (node (ref "D34") (pin "CKO") (pinfunction "CO_CKO") (pintype "bidirectional"))
      (node (ref "D35") (pin "CKI") (pinfunction "CI_CKI") (pintype "bidirectional"))
    )
    (net (code "82") (name "Net-(D34-DO)") (class "Default")
      (node (ref "D34") (pin "SDO") (pinfunction "DO_SDO") (pintype "bidirectional"))
      (node (ref "D35") (pin "SDI") (pinfunction "DI_SDI") (pintype "bidirectional"))
    )
    (net (code "83") (name "Net-(D35-CO)") (class "Default")
      (node (ref "D35") (pin "CKO") (pinfunction "CO_CKO") (pintype "bidirectional"))
      (node (ref "D36") (pin "CKI") (pinfunction "CI_CKI") (pintype "bidirectional"))
    )
    (net (code "84") (name "Net-(D35-DO)") (class "Default")
      (node (ref "D35") (pin "SDO") (pinfunction "DO_SDO") (pintype "bidirectional"))
      (node (ref "D36") (pin "SDI") (pinfunction "DI_SDI") (pintype "bidirectional"))
    )
    (net (code "85") (name "Net-(D37-CO)") (class "Default")
      (node (ref "D37") (pin "CKO") (pinfunction "CO_CKO") (pintype "bidirectional"))
      (node (ref "D38") (pin "CKI") (pinfunction "CI_CKI") (pintype "bidirectional"))
    )
    (net (code "86") (name "Net-(D37-DO)") (class "Default")
      (node (ref "D37") (pin "SDO") (pinfunction "DO_SDO") (pintype "bidirectional"))
      (node (ref "D38") (pin "SDI") (pinfunction "DI_SDI") (pintype "bidirectional"))
    )
    (net (code "87") (name "Net-(D38-CO)") (class "Default")
      (node (ref "D38") (pin "CKO") (pinfunction "CO_CKO") (pintype "bidirectional"))
      (node (ref "D39") (pin "CKI") (pinfunction "CI_CKI") (pintype "bidirectional"))
    )
    (net (code "88") (name "Net-(D38-DO)") (class "Default")
      (node (ref "D38") (pin "SDO") (pinfunction "DO_SDO") (pintype "bidirectional"))
      (node (ref "D39") (pin "SDI") (pinfunction "DI_SDI") (pintype "bidirectional"))
    )
    (net (code "89") (name "Net-(D39-CO)") (class "Default")
      (node (ref "D39") (pin "CKO") (pinfunction "CO_CKO") (pintype "bidirectional"))
      (node (ref "D40") (pin "CKI") (pinfunction "CI_CKI") (pintype "bidirectional"))
    )
    (net (code "90") (name "Net-(D39-DO)") (class "Default")
      (node (ref "D39") (pin "SDO") (pinfunction "DO_SDO") (pintype "bidirectional"))
      (node (ref "D40") (pin "SDI") (pinfunction "DI_SDI") (pintype "bidirectional"))
    )
    (net (code "91") (name "Net-(D40-CO)") (class "Default")
      (node (ref "D40") (pin "CKO") (pinfunction "CO_CKO") (pintype "bidirectional"))
      (node (ref "D41") (pin "CKI") (pinfunction "CI_CKI") (pintype "bidirectional"))
    )
    (net (code "92") (name "Net-(D40-DO)") (class "Default")
      (node (ref "D40") (pin "SDO") (pinfunction "DO_SDO") (pintype "bidirectional"))
      (node (ref "D41") (pin "SDI") (pinfunction "DI_SDI") (pintype "bidirectional"))
    )
    (net (code "93") (name "Net-(D41-CO)") (class "Default")
      (node (ref "D41") (pin "CKO") (pinfunction "CO_CKO") (pintype "bidirectional"))
      (node (ref "D42") (pin "CKI") (pinfunction "CI_CKI") (pintype "bidirectional"))
    )
    (net (code "94") (name "Net-(D41-DO)") (class "Default")
      (node (ref "D41") (pin "SDO") (pinfunction "DO_SDO") (pintype "bidirectional"))
      (node (ref "D42") (pin "SDI") (pinfunction "DI_SDI") (pintype "bidirectional"))
    )
    (net (code "95") (name "Net-(D42-CO)") (class "Default")
      (node (ref "D42") (pin "CKO") (pinfunction "CO_CKO") (pintype "bidirectional"))
      (node (ref "D43") (pin "CKI") (pinfunction "CI_CKI") (pintype "bidirectional"))
    )
    (net (code "96") (name "Net-(D42-DO)") (class "Default")
      (node (ref "D42") (pin "SDO") (pinfunction "DO_SDO") (pintype "bidirectional"))
      (node (ref "D43") (pin "SDI") (pinfunction "DI_SDI") (pintype "bidirectional"))
    )
    (net (code "97") (name "Net-(D43-CO)") (class "Default")
      (node (ref "D43") (pin "CKO") (pinfunction "CO_CKO") (pintype "bidirectional"))
      (node (ref "D44") (pin "CKI") (pinfunction "CI_CKI") (pintype "bidirectional"))
    )
    (net (code "98") (name "Net-(D43-DO)") (class "Default")
      (node (ref "D43") (pin "SDO") (pinfunction "DO_SDO") (pintype "bidirectional"))
      (node (ref "D44") (pin "SDI") (pinfunction "DI_SDI") (pintype "bidirectional"))
    )
    (net (code "99") (name "Net-(D44-CO)") (class "Default")
      (node (ref "D44") (pin "CKO") (pinfunction "CO_CKO") (pintype "bidirectional"))
      (node (ref "D45") (pin "CKI") (pinfunction "CI_CKI") (pintype "bidirectional"))
    )
    (net (code "100") (name "Net-(D44-DO)") (class "Default")
      (node (ref "D44") (pin "SDO") (pinfunction "DO_SDO") (pintype "bidirectional"))
      (node (ref "D45") (pin "SDI") (pinfunction "DI_SDI") (pintype "bidirectional"))
    )
    (net (code "101") (name "Net-(D46-CO)") (class "Default")
      (node (ref "D46") (pin "CKO") (pinfunction "CO_CKO") (pintype "bidirectional"))
      (node (ref "D47") (pin "CKI") (pinfunction "CI_CKI") (pintype "bidirectional"))
    )
    (net (code "102") (name "Net-(D46-DO)") (class "Default")
      (node (ref "D46") (pin "SDO") (pinfunction "DO_SDO") (pintype "bidirectional"))
      (node (ref "D47") (pin "SDI") (pinfunction "DI_SDI") (pintype "bidirectional"))
    )
    (net (code "103") (name "Net-(D47-CO)") (class "Default")
      (node (ref "D47") (pin "CKO") (pinfunction "CO_CKO") (pintype "bidirectional"))
      (node (ref "D48") (pin "CKI") (pinfunction "CI_CKI") (pintype "bidirectional"))
    )
    (net (code "104") (name "Net-(D47-DO)") (class "Default")
      (node (ref "D47") (pin "SDO") (pinfunction "DO_SDO") (pintype "bidirectional"))
      (node (ref "D48") (pin "SDI") (pinfunction "DI_SDI") (pintype "bidirectional"))
    )
    (net (code "105") (name "Net-(D48-CO)") (class "Default")
      (node (ref "D48") (pin "CKO") (pinfunction "CO_CKO") (pintype "bidirectional"))
      (node (ref "D49") (pin "CKI") (pinfunction "CI_CKI") (pintype "bidirectional"))
    )
    (net (code "106") (name "Net-(D48-DO)") (class "Default")
      (node (ref "D48") (pin "SDO") (pinfunction "DO_SDO") (pintype "bidirectional"))
      (node (ref "D49") (pin "SDI") (pinfunction "DI_SDI") (pintype "bidirectional"))
    )
    (net (code "107") (name "Net-(D49-CO)") (class "Default")
      (node (ref "D49") (pin "CKO") (pinfunction "CO_CKO") (pintype "bidirectional"))
      (node (ref "D50") (pin "CKI") (pinfunction "CI_CKI") (pintype "bidirectional"))
    )
    (net (code "108") (name "Net-(D49-DO)") (class "Default")
      (node (ref "D49") (pin "SDO") (pinfunction "DO_SDO") (pintype "bidirectional"))
      (node (ref "D50") (pin "SDI") (pinfunction "DI_SDI") (pintype "bidirectional"))
    )
    (net (code "109") (name "Net-(D50-CO)") (class "Default")
      (node (ref "D50") (pin "CKO") (pinfunction "CO_CKO") (pintype "bidirectional"))
      (node (ref "D51") (pin "CKI") (pinfunction "CI_CKI") (pintype "bidirectional"))
    )
    (net (code "110") (name "Net-(D50-DO)") (class "Default")
      (node (ref "D50") (pin "SDO") (pinfunction "DO_SDO") (pintype "bidirectional"))
      (node (ref "D51") (pin "SDI") (pinfunction "DI_SDI") (pintype "bidirectional"))
    )
    (net (code "111") (name "Net-(D51-CO)") (class "Default")
      (node (ref "D51") (pin "CKO") (pinfunction "CO_CKO") (pintype "bidirectional"))
      (node (ref "D52") (pin "CKI") (pinfunction "CI_CKI") (pintype "bidirectional"))
    )
    (net (code "112") (name "Net-(D51-DO)") (class "Default")
      (node (ref "D51") (pin "SDO") (pinfunction "DO_SDO") (pintype "bidirectional"))
      (node (ref "D52") (pin "SDI") (pinfunction "DI_SDI") (pintype "bidirectional"))
    )
    (net (code "113") (name "Net-(D52-CO)") (class "Default")
      (node (ref "D52") (pin "CKO") (pinfunction "CO_CKO") (pintype "bidirectional"))
      (node (ref "D53") (pin "CKI") (pinfunction "CI_CKI") (pintype "bidirectional"))
    )
    (net (code "114") (name "Net-(D52-DO)") (class "Default")
      (node (ref "D52") (pin "SDO") (pinfunction "DO_SDO") (pintype "bidirectional"))
      (node (ref "D53") (pin "SDI") (pinfunction "DI_SDI") (pintype "bidirectional"))
    )
    (net (code "115") (name "Net-(D53-CO)") (class "Default")
      (node (ref "D53") (pin "CKO") (pinfunction "CO_CKO") (pintype "bidirectional"))
      (node (ref "D54") (pin "CKI") (pinfunction "CI_CKI") (pintype "bidirectional"))
    )
    (net (code "116") (name "Net-(D53-DO)") (class "Default")
      (node (ref "D53") (pin "SDO") (pinfunction "DO_SDO") (pintype "bidirectional"))
      (node (ref "D54") (pin "SDI") (pinfunction "DI_SDI") (pintype "bidirectional"))
    )
    (net (code "117") (name "Net-(D55-CO)") (class "Default")
      (node (ref "D55") (pin "CKO") (pinfunction "CO_CKO") (pintype "bidirectional"))
      (node (ref "D56") (pin "CKI") (pinfunction "CI_CKI") (pintype "bidirectional"))
    )
    (net (code "118") (name "Net-(D55-DO)") (class "Default")
      (node (ref "D55") (pin "SDO") (pinfunction "DO_SDO") (pintype "bidirectional"))
      (node (ref "D56") (pin "SDI") (pinfunction "DI_SDI") (pintype "bidirectional"))
    )
    (net (code "119") (name "Net-(D56-CO)") (class "Default")
      (node (ref "D56") (pin "CKO") (pinfunction "CO_CKO") (pintype "bidirectional"))
      (node (ref "D57") (pin "CKI") (pinfunction "CI_CKI") (pintype "bidirectional"))
    )
    (net (code "120") (name "Net-(D56-DO)") (class "Default")
      (node (ref "D56") (pin "SDO") (pinfunction "DO_SDO") (pintype "bidirectional"))
      (node (ref "D57") (pin "SDI") (pinfunction "DI_SDI") (pintype "bidirectional"))
    )
    (net (code "121") (name "Net-(D57-CO)") (class "Default")
      (node (ref "D57") (pin "CKO") (pinfunction "CO_CKO") (pintype "bidirectional"))
      (node (ref "D58") (pin "CKI") (pinfunction "CI_CKI") (pintype "bidirectional"))
    )
    (net (code "122") (name "Net-(D57-DO)") (class "Default")
      (node (ref "D57") (pin "SDO") (pinfunction "DO_SDO") (pintype "bidirectional"))
      (node (ref "D58") (pin "SDI") (pinfunction "DI_SDI") (pintype "bidirectional"))
    )
    (net (code "123") (name "Net-(D58-CO)") (class "Default")
      (node (ref "D58") (pin "CKO") (pinfunction "CO_CKO") (pintype "bidirectional"))
      (node (ref "D59") (pin "CKI") (pinfunction "CI_CKI") (pintype "bidirectional"))
    )
    (net (code "124") (name "Net-(D58-DO)") (class "Default")
      (node (ref "D58") (pin "SDO") (pinfunction "DO_SDO") (pintype "bidirectional"))
      (node (ref "D59") (pin "SDI") (pinfunction "DI_SDI") (pintype "bidirectional"))
    )
    (net (code "125") (name "Net-(D59-CO)") (class "Default")
      (node (ref "D59") (pin "CKO") (pinfunction "CO_CKO") (pintype "bidirectional"))
      (node (ref "D60") (pin "CKI") (pinfunction "CI_CKI") (pintype "bidirectional"))
    )
    (net (code "126") (name "Net-(D59-DO)") (class "Default")
      (node (ref "D59") (pin "SDO") (pinfunction "DO_SDO") (pintype "bidirectional"))
      (node (ref "D60") (pin "SDI") (pinfunction "DI_SDI") (pintype "bidirectional"))
    )
    (net (code "127") (name "Net-(D60-CO)") (class "Default")
      (node (ref "D60") (pin "CKO") (pinfunction "CO_CKO") (pintype "bidirectional"))
      (node (ref "D61") (pin "CKI") (pinfunction "CI_CKI") (pintype "bidirectional"))
    )
    (net (code "128") (name "Net-(D60-DO)") (class "Default")
      (node (ref "D60") (pin "SDO") (pinfunction "DO_SDO") (pintype "bidirectional"))
      (node (ref "D61") (pin "SDI") (pinfunction "DI_SDI") (pintype "bidirectional"))
    )
    (net (code "129") (name "Net-(D61-CO)") (class "Default")
      (node (ref "D61") (pin "CKO") (pinfunction "CO_CKO") (pintype "bidirectional"))
      (node (ref "D62") (pin "CKI") (pinfunction "CI_CKI") (pintype "bidirectional"))
    )
    (net (code "130") (name "Net-(D61-DO)") (class "Default")
      (node (ref "D61") (pin "SDO") (pinfunction "DO_SDO") (pintype "bidirectional"))
      (node (ref "D62") (pin "SDI") (pinfunction "DI_SDI") (pintype "bidirectional"))
    )
    (net (code "131") (name "Net-(D62-CO)") (class "Default")
      (node (ref "D62") (pin "CKO") (pinfunction "CO_CKO") (pintype "bidirectional"))
      (node (ref "D63") (pin "CKI") (pinfunction "CI_CKI") (pintype "bidirectional"))
    )
    (net (code "132") (name "Net-(D62-DO)") (class "Default")
      (node (ref "D62") (pin "SDO") (pinfunction "DO_SDO") (pintype "bidirectional"))
      (node (ref "D63") (pin "SDI") (pinfunction "DI_SDI") (pintype "bidirectional"))
    )
  )
)
